# Water_SmartSchematicV1.net
KiCad netlist of a schematic drawn in Altium Designer
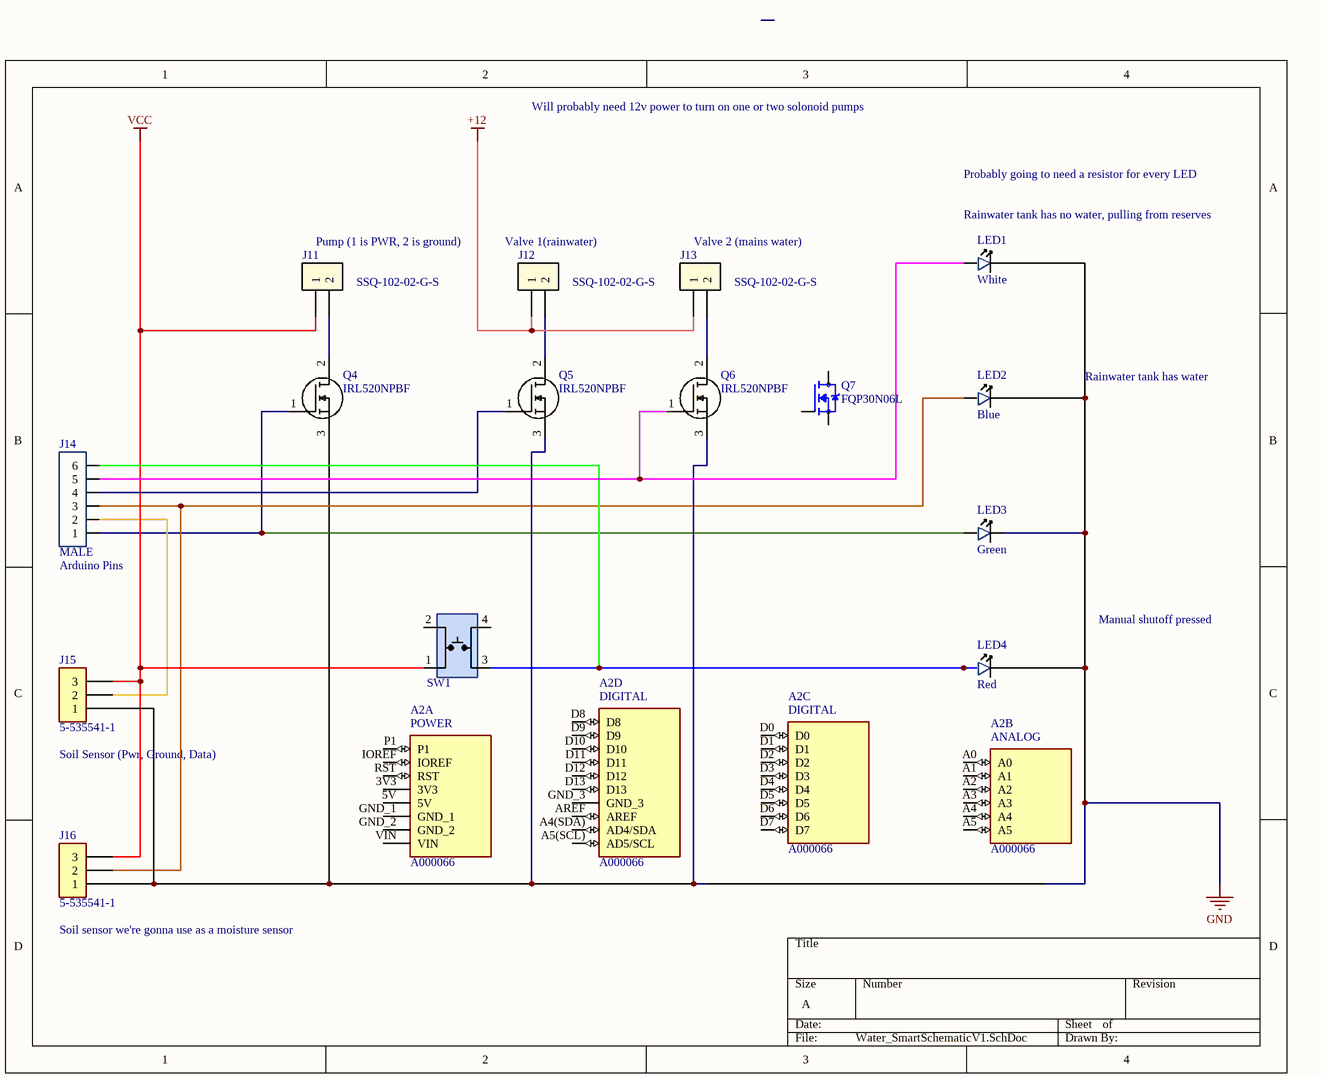
[diagram p0: Water_SmartSchematicV1.SchDoc]

(export (version "E")
  (design (tool "Eeschema 10.0.6"))
  (components
    (comp (ref "A2")
      (value "A000066")
      (footprint "ARDUINO_A000066")
      (description "Microcontroller board based on the ATmega328P.")
      (fields (field (name "MF") "Arduino") (field (name "MP") "Arduino Uno Rev3"))
      (libsource (lib "A000066") (part "A000066"))
    )
    (comp (ref "J11")
      (value "SSQ-102-02-G-S")
      (footprint "JF-2_1X2_TU_SSQ")
      (description "2.54mm Straight 1x2P 2 1 Straight,P=2.54mm  Female Headers ROHSon Available")
      (fields (field (name "MFR PART #") "C49661"))
      (libsource (lib "ECEN5730Lib_2023_05_DS (1)") (part "JF_2_PIN_FEMALE"))
    )
    (comp (ref "J12")
      (value "SSQ-102-02-G-S")
      (footprint "JF-2_1X2_TU_SSQ")
      (description "2.54mm Straight 1x2P 2 1 Straight,P=2.54mm  Female Headers ROHSon Available")
      (fields (field (name "MFR PART #") "C49661"))
      (libsource (lib "ECEN5730Lib_2023_05_DS (1)") (part "JF_2_PIN_FEMALE"))
    )
    (comp (ref "J13")
      (value "SSQ-102-02-G-S")
      (footprint "JF-2_1X2_TU_SSQ")
      (description "2.54mm Straight 1x2P 2 1 Straight,P=2.54mm  Female Headers ROHSon Available")
      (fields (field (name "MFR PART #") "C49661"))
      (libsource (lib "ECEN5730Lib_2023_05_DS (1)") (part "JF_2_PIN_FEMALE"))
    )
    (comp (ref "J14")
      (value "MALE")
      (footprint "6_PIN_100MIL-Male")
      (description "Male header- 6 pin 1 row- through Hole")
      (fields (field (name "LCSC PART#") "C37208"))
      (libsource (lib "ECEN5730Lib_2023_05_DS (1)") (part "JM_6_PIN_MALE"))
    )
    (comp (ref "J15")
      (value "5-535541-1")
      (footprint "JF_TE_5-535541-1")
      (description "Conn Socket Strip RCP 3 POS 2.54mm Solder ST Thru-Hole")
      (fields (field (name "MFR PART #") "PM2.54-1*3") (field (name "LCSC PART#") "C5116529"))
      (libsource (lib "ECEN5730Lib_2023_05_DS (1)") (part "JF_3_PIN_FEMALE"))
    )
    (comp (ref "J16")
      (value "5-535541-1")
      (footprint "JF_TE_5-535541-1")
      (description "Conn Socket Strip RCP 3 POS 2.54mm Solder ST Thru-Hole")
      (fields (field (name "MFR PART #") "PM2.54-1*3") (field (name "LCSC PART#") "C5116529"))
      (libsource (lib "ECEN5730Lib_2023_05_DS (1)") (part "JF_3_PIN_FEMALE"))
    )
    (comp (ref "LED1")
      (value "White")
      (footprint "LED_1206")
      (description "White light 1206  Light Emitting Diodes (LED) ROHS")
      (fields (field (name "LCSC PART#") "C130718") (field (name "MFR PART #") "NCD1206W1"))
      (libsource (lib "ECEN5730Lib_2023_05_DS (1)") (part "LED_WHITE_1206"))
    )
    (comp (ref "LED2")
      (value "Blue")
      (footprint "LED_1206")
      (description "blue 1206  Light Emitting Diodes (LED) ROHS")
      (fields (field (name "MFR PART #") "NCD1206B1") (field (name "LCSC PART#") "C130717"))
      (libsource (lib "ECEN5730Lib_2023_05_DS (1)") (part "LED_BLUE_1206"))
    )
    (comp (ref "LED3")
      (value "Green")
      (footprint "LED_1206")
      (description "Green 513~528nm 1206 Light Emitting Diodes (LED) RoHS")
      (fields (field (name "MFR PART #") "SZYY1206G") (field (name "LCSC PART#") "C434439"))
      (libsource (lib "ECEN5730Lib_2023_05_DS (1)") (part "LED_GREEN_1206"))
    )
    (comp (ref "LED4")
      (value "Red")
      (footprint "LED_1206")
      (description "Red 621~631nm 1206 Light Emitting Diodes (LED) RoHS")
      (fields (field (name "MFR PART #") "15-21/R6C-FQ1R1B/2T") (field (name "LCSC PART#") "C93133"))
      (libsource (lib "ECEN5730Lib_2023_05_DS (1)") (part "LED_RED_1206"))
    )
    (comp (ref "Q4")
      (value "IRL520NPBF")
      (footprint "TO254P469X1042X1967-3P")
      (description "MOSFET (N-Channel)  IRL520NPBF")
      (fields (field (name "MOUSER PART NUMBER") "942-IRL520NPBF"))
      (libsource (lib "ECEN5730Lib_2023_05_DS (1)") (part "Q_Nch_MOSFET_PTH"))
    )
    (comp (ref "Q5")
      (value "IRL520NPBF")
      (footprint "TO254P469X1042X1967-3P")
      (description "MOSFET (N-Channel)  IRL520NPBF")
      (fields (field (name "MOUSER PART NUMBER") "942-IRL520NPBF"))
      (libsource (lib "ECEN5730Lib_2023_05_DS (1)") (part "Q_Nch_MOSFET_PTH"))
    )
    (comp (ref "Q6")
      (value "IRL520NPBF")
      (footprint "TO254P469X1042X1967-3P")
      (description "MOSFET (N-Channel)  IRL520NPBF")
      (fields (field (name "MOUSER PART NUMBER") "942-IRL520NPBF"))
      (libsource (lib "ECEN5730Lib_2023_05_DS (1)") (part "Q_Nch_MOSFET_PTH"))
    )
    (comp (ref "Q7")
      (value "FQP30N06L")
      (footprint "TO220V")
      (description "N-Channel 60V 32A _Tc_ 79W _Tc_ Through Hole TO-220-3")
      (fields (field (name "MF") "ON Semiconductor"))
      (libsource (lib "FQP30N06L") (part "FQP30N06L"))
    )
    (comp (ref "SW1")
      (value "TL3305AF160QG")
      (footprint "Switch_JLC")
      (description "Tactile Switch SPST-NO Top Actuated Surface Mount")
      (fields (field (name "MFR PART #") "KH-4.5X4.5X4.3H-STM") (field (name "LCSC PART#") "C2837550"))
      (libsource (lib "ECEN5730Lib_2023_05_DS (1)") (part "SW_Push_Button_JLC"))
    )
  )
  (nets
    (net (code "1") (name "+12") (class "Default")
      (node (ref "J12") (pin "1") (pinfunction "1_1") (pintype "passive"))
      (node (ref "J13") (pin "1") (pinfunction "1_1") (pintype "passive"))
    )
    (net (code "2") (name "GND") (class "Default")
      (node (ref "J15") (pin "1") (pinfunction "1_1") (pintype "passive"))
      (node (ref "J16") (pin "1") (pinfunction "1_1") (pintype "passive"))
      (node (ref "LED1") (pin "2") (pinfunction "2_2") (pintype "passive"))
      (node (ref "LED2") (pin "2") (pinfunction "2_2") (pintype "passive"))
      (node (ref "LED3") (pin "2") (pinfunction "2_2") (pintype "passive"))
      (node (ref "LED4") (pin "2") (pinfunction "2_2") (pintype "passive"))
      (node (ref "Q4") (pin "3") (pinfunction "S_3") (pintype "passive"))
      (node (ref "Q5") (pin "3") (pinfunction "S_3") (pintype "passive"))
      (node (ref "Q6") (pin "3") (pinfunction "S_3") (pintype "passive"))
    )
    (net (code "3") (name "Net-(J14-Pad2)") (class "Default")
      (node (ref "J14") (pin "2") (pinfunction "2_2") (pintype "passive"))
      (node (ref "J15") (pin "2") (pinfunction "2_2") (pintype "passive"))
    )
    (net (code "4") (name "Net-(J14-Pad3)") (class "Default")
      (node (ref "J14") (pin "3") (pinfunction "3_3") (pintype "passive"))
      (node (ref "J16") (pin "2") (pinfunction "2_2") (pintype "passive"))
      (node (ref "LED2") (pin "1") (pinfunction "1_1") (pintype "passive"))
    )
    (net (code "5") (name "Net-(J14-Pad6)") (class "Default")
      (node (ref "J14") (pin "6") (pinfunction "6_6") (pintype "passive"))
      (node (ref "LED4") (pin "1") (pinfunction "1_1") (pintype "passive"))
      (node (ref "SW1") (pin "3") (pinfunction "3_3") (pintype "passive"))
    )
    (net (code "6") (name "Net-(Q4-D)") (class "Default")
      (node (ref "J11") (pin "2") (pinfunction "2_2") (pintype "passive"))
      (node (ref "Q4") (pin "2") (pinfunction "D_2") (pintype "passive"))
    )
    (net (code "7") (name "Net-(Q4-G)") (class "Default")
      (node (ref "J14") (pin "1") (pinfunction "1_1") (pintype "passive"))
      (node (ref "LED3") (pin "1") (pinfunction "1_1") (pintype "passive"))
      (node (ref "Q4") (pin "1") (pinfunction "G_1") (pintype "passive"))
    )
    (net (code "8") (name "Net-(Q5-D)") (class "Default")
      (node (ref "J12") (pin "2") (pinfunction "2_2") (pintype "passive"))
      (node (ref "Q5") (pin "2") (pinfunction "D_2") (pintype "passive"))
    )
    (net (code "9") (name "Net-(Q5-G)") (class "Default")
      (node (ref "J14") (pin "4") (pinfunction "4_4") (pintype "passive"))
      (node (ref "Q5") (pin "1") (pinfunction "G_1") (pintype "passive"))
    )
    (net (code "10") (name "Net-(Q6-D)") (class "Default")
      (node (ref "J13") (pin "2") (pinfunction "2_2") (pintype "passive"))
      (node (ref "Q6") (pin "2") (pinfunction "D_2") (pintype "passive"))
    )
    (net (code "11") (name "Net-(Q6-G)") (class "Default")
      (node (ref "J14") (pin "5") (pinfunction "5_5") (pintype "passive"))
      (node (ref "LED1") (pin "1") (pinfunction "1_1") (pintype "passive"))
      (node (ref "Q6") (pin "1") (pinfunction "G_1") (pintype "passive"))
    )
    (net (code "12") (name "VCC") (class "Default")
      (node (ref "J11") (pin "1") (pinfunction "1_1") (pintype "passive"))
      (node (ref "J15") (pin "3") (pinfunction "3_3") (pintype "passive"))
      (node (ref "J16") (pin "3") (pinfunction "3_3") (pintype "passive"))
      (node (ref "SW1") (pin "1") (pinfunction "1_1") (pintype "passive"))
    )
    (net (code "13") (name "unconnected-(A2-Pad3V3)") (class "Default")
      (node (ref "A2") (pin "3V3") (pinfunction "3V3_3V3") (pintype "power_in"))
    )
    (net (code "14") (name "unconnected-(A2-Pad5V)") (class "Default")
      (node (ref "A2") (pin "5V") (pinfunction "5V_5V") (pintype "power_in"))
    )
    (net (code "15") (name "unconnected-(A2-PadA0)") (class "Default")
      (node (ref "A2") (pin "A0") (pinfunction "A0_A0") (pintype "bidirectional"))
    )
    (net (code "16") (name "unconnected-(A2-PadA1)") (class "Default")
      (node (ref "A2") (pin "A1") (pinfunction "A1_A1") (pintype "bidirectional"))
    )
    (net (code "17") (name "unconnected-(A2-PadA2)") (class "Default")
      (node (ref "A2") (pin "A2") (pinfunction "A2_A2") (pintype "bidirectional"))
    )
    (net (code "18") (name "unconnected-(A2-PadA3)") (class "Default")
      (node (ref "A2") (pin "A3") (pinfunction "A3_A3") (pintype "bidirectional"))
    )
    (net (code "19") (name "unconnected-(A2-PadA4)") (class "Default")
      (node (ref "A2") (pin "A4") (pinfunction "A4_A4") (pintype "bidirectional"))
    )
    (net (code "20") (name "unconnected-(A2-PadA5)") (class "Default")
      (node (ref "A2") (pin "A5") (pinfunction "A5_A5") (pintype "bidirectional"))
    )
    (net (code "21") (name "unconnected-(A2-PadAREF)") (class "Default")
      (node (ref "A2") (pin "AREF") (pinfunction "AREF_AREF") (pintype "bidirectional"))
    )
    (net (code "22") (name "unconnected-(A2-PadD0)") (class "Default")
      (node (ref "A2") (pin "D0") (pinfunction "D0_D0") (pintype "bidirectional"))
    )
    (net (code "23") (name "unconnected-(A2-PadD1)") (class "Default")
      (node (ref "A2") (pin "D1") (pinfunction "D1_D1") (pintype "bidirectional"))
    )
    (net (code "24") (name "unconnected-(A2-PadD2)") (class "Default")
      (node (ref "A2") (pin "D2") (pinfunction "D2_D2") (pintype "bidirectional"))
    )
    (net (code "25") (name "unconnected-(A2-PadD3)") (class "Default")
      (node (ref "A2") (pin "D3") (pinfunction "D3_D3") (pintype "bidirectional"))
    )
    (net (code "26") (name "unconnected-(A2-PadD4)") (class "Default")
      (node (ref "A2") (pin "D4") (pinfunction "D4_D4") (pintype "bidirectional"))
    )
    (net (code "27") (name "unconnected-(A2-PadD5)") (class "Default")
      (node (ref "A2") (pin "D5") (pinfunction "D5_D5") (pintype "bidirectional"))
    )
    (net (code "28") (name "unconnected-(A2-PadD6)") (class "Default")
      (node (ref "A2") (pin "D6") (pinfunction "D6_D6") (pintype "bidirectional"))
    )
    (net (code "29") (name "unconnected-(A2-PadD7)") (class "Default")
      (node (ref "A2") (pin "D7") (pinfunction "D7_D7") (pintype "bidirectional"))
    )
    (net (code "30") (name "unconnected-(A2-PadD8)") (class "Default")
      (node (ref "A2") (pin "D8") (pinfunction "D8_D8") (pintype "bidirectional"))
    )
    (net (code "31") (name "unconnected-(A2-PadD9)") (class "Default")
      (node (ref "A2") (pin "D9") (pinfunction "D9_D9") (pintype "bidirectional"))
    )
    (net (code "32") (name "unconnected-(A2-PadD10)") (class "Default")
      (node (ref "A2") (pin "D10") (pinfunction "D10_D10") (pintype "bidirectional"))
    )
    (net (code "33") (name "unconnected-(A2-PadD11)") (class "Default")
      (node (ref "A2") (pin "D11") (pinfunction "D11_D11") (pintype "bidirectional"))
    )
    (net (code "34") (name "unconnected-(A2-PadD12)") (class "Default")
      (node (ref "A2") (pin "D12") (pinfunction "D12_D12") (pintype "bidirectional"))
    )
    (net (code "35") (name "unconnected-(A2-PadD13)") (class "Default")
      (node (ref "A2") (pin "D13") (pinfunction "D13_D13") (pintype "bidirectional"))
    )
    (net (code "36") (name "unconnected-(A2-PadGND_1)") (class "Default")
      (node (ref "A2") (pin "GND_1") (pinfunction "GND_1_GND_1") (pintype "power_in"))
    )
    (net (code "37") (name "unconnected-(A2-PadGND_2)") (class "Default")
      (node (ref "A2") (pin "GND_2") (pinfunction "GND_2_GND_2") (pintype "power_in"))
    )
    (net (code "38") (name "unconnected-(A2-PadGND_3)") (class "Default")
      (node (ref "A2") (pin "GND_3") (pinfunction "GND_3_GND_3") (pintype "power_in"))
    )
    (net (code "39") (name "unconnected-(A2-PadIOREF)") (class "Default")
      (node (ref "A2") (pin "IOREF") (pinfunction "IOREF_IOREF") (pintype "bidirectional"))
    )
    (net (code "40") (name "unconnected-(A2-PadP1)") (class "Default")
      (node (ref "A2") (pin "P1") (pinfunction "P1_P1") (pintype "bidirectional"))
    )
    (net (code "41") (name "unconnected-(A2-PadRST)") (class "Default")
      (node (ref "A2") (pin "RST") (pinfunction "RST_RST") (pintype "bidirectional"))
    )
    (net (code "42") (name "unconnected-(A2-PadVIN)") (class "Default")
      (node (ref "A2") (pin "VIN") (pinfunction "VIN_VIN") (pintype "power_in"))
    )
    (net (code "43") (name "unconnected-(A2D-AD4{slash}SDA-PadA4(SDA))") (class "Default")
      (node (ref "A2") (pin "A4(SDA)") (pinfunction "AD4/SDA_A4(SDA)") (pintype "bidirectional"))
    )
    (net (code "44") (name "unconnected-(A2D-AD5{slash}SCL-PadA5(SCL))") (class "Default")
      (node (ref "A2") (pin "A5(SCL)") (pinfunction "AD5/SCL_A5(SCL)") (pintype "bidirectional"))
    )
    (net (code "45") (name "unconnected-(Q7-D-Pad2)") (class "Default")
      (node (ref "Q7") (pin "2") (pinfunction "D_2") (pintype "passive"))
    )
    (net (code "46") (name "unconnected-(Q7-G-Pad1)") (class "Default")
      (node (ref "Q7") (pin "1") (pinfunction "G_1") (pintype "passive"))
    )
    (net (code "47") (name "unconnected-(Q7-S-Pad3)") (class "Default")
      (node (ref "Q7") (pin "3") (pinfunction "S_3") (pintype "passive"))
    )
    (net (code "48") (name "unconnected-(SW1-Pad2)") (class "Default")
      (node (ref "SW1") (pin "2") (pinfunction "2_2") (pintype "passive"))
    )
    (net (code "49") (name "unconnected-(SW1-Pad4)") (class "Default")
      (node (ref "SW1") (pin "4") (pinfunction "4_4") (pintype "passive"))
    )
  )
)
